# top.net
KiCad netlist of a schematic drawn in EAGLE
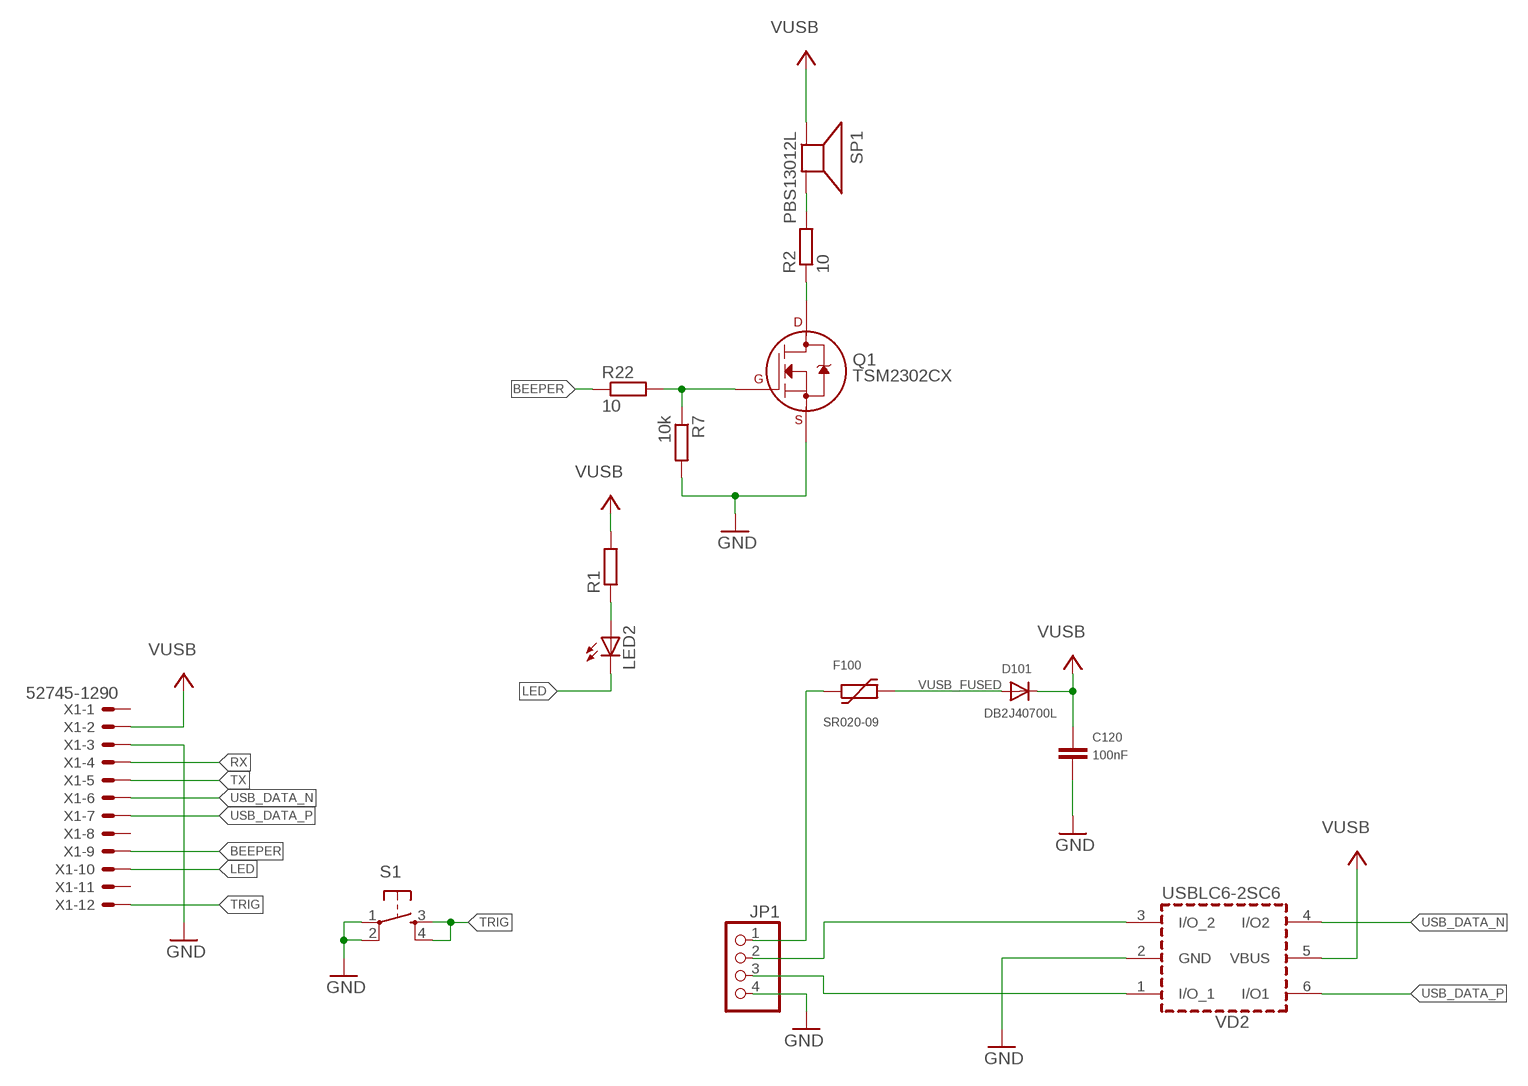
[diagram p0: schematic, sheet 1]

(export (version "E")
  (design (tool "Eeschema 10.0.6"))
  (components
    (comp (ref "C120")
      (value "100nF")
      (footprint "eagle-import:C0603K")
      (libsource (lib "eagle-import") (part "C-EUC0603K"))
    )
    (comp (ref "D101")
      (value "DB2J40700L")
      (footprint "eagle-import:SOD-323F")
      (libsource (lib "eagle-import") (part "DIODESOD-323F"))
    )
    (comp (ref "F100")
      (value "SR020-09")
      (footprint "eagle-import:PTC0805")
      (libsource (lib "eagle-import") (part "FUSE_PTC-0805"))
    )
    (comp (ref "JP1")
      (value "PINHD-1X4")
      (footprint "eagle-import:1X04")
      (libsource (lib "eagle-import") (part "PINHD-1X4"))
    )
    (comp (ref "LED2")
      (value "LEDCHIP-LED0805")
      (footprint "eagle-import:CHIP-LED0805")
      (libsource (lib "eagle-import") (part "LEDCHIP-LED0805"))
    )
    (comp (ref "Q1")
      (value "TSM2302CX")
      (footprint "eagle-import:SOT-23")
      (libsource (lib "eagle-import") (part "2N700_SOT232A"))
    )
    (comp (ref "R1")
      (value "R-EU_R0603")
      (footprint "eagle-import:R0603")
      (libsource (lib "eagle-import") (part "R-EU_R0603"))
    )
    (comp (ref "R2")
      (value "10")
      (footprint "eagle-import:R0603")
      (libsource (lib "eagle-import") (part "R-EU_R0603"))
    )
    (comp (ref "R7")
      (value "10k")
      (footprint "eagle-import:R0603")
      (libsource (lib "eagle-import") (part "R-EU_R0603"))
    )
    (comp (ref "R22")
      (value "10")
      (footprint "eagle-import:R0603")
      (libsource (lib "eagle-import") (part "R-EU_R0603"))
    )
    (comp (ref "S1")
      (value "TAC_SWITCHSMD")
      (footprint "eagle-import:TACTILE_SWITCH_SMD")
      (libsource (lib "eagle-import") (part "TAC_SWITCHSMD"))
    )
    (comp (ref "SP1")
      (value "PBS13012L")
      (footprint "eagle-import:AL60P")
      (libsource (lib "eagle-import") (part "SPEAKER/AL60P"))
    )
    (comp (ref "VD2")
      (value "USBLC6-2SC6")
      (footprint "eagle-import:SOT-23-6L")
      (libsource (lib "eagle-import") (part "USBLC6-2SC6"))
    )
    (comp (ref "X1")
      (value "52745-1290")
      (footprint "eagle-import:52745-1290")
      (libsource (lib "eagle-import") (part "52745-1290"))
    )
  )
  (nets
    (net (code "1") (name "/VUSB_FUSED") (class "Default")
      (node (ref "D101") (pin "A") (pinfunction "A_A") (pintype "passive"))
      (node (ref "F100") (pin "2") (pinfunction "2_2") (pintype "passive"))
    )
    (net (code "2") (name "BEEPER") (class "Default")
      (node (ref "R22") (pin "1") (pinfunction "1_1") (pintype "passive"))
      (node (ref "X1") (pin "9") (pinfunction "S_9") (pintype "passive"))
    )
    (net (code "3") (name "GND") (class "Default")
      (node (ref "C120") (pin "2") (pinfunction "2_2") (pintype "passive"))
      (node (ref "JP1") (pin "4") (pinfunction "4_4") (pintype "passive"))
      (node (ref "Q1") (pin "2") (pinfunction "S_2") (pintype "bidirectional"))
      (node (ref "R7") (pin "2") (pinfunction "2_2") (pintype "passive"))
      (node (ref "S1") (pin "1") (pinfunction "1_1") (pintype "passive"))
      (node (ref "S1") (pin "2") (pinfunction "2_2") (pintype "passive"))
      (node (ref "VD2") (pin "2") (pinfunction "GND_2") (pintype "bidirectional"))
      (node (ref "X1") (pin "3") (pinfunction "S_3") (pintype "passive"))
    )
    (net (code "4") (name "LED") (class "Default")
      (node (ref "LED2") (pin "C") (pinfunction "C_C") (pintype "passive"))
      (node (ref "X1") (pin "10") (pinfunction "S_10") (pintype "passive"))
    )
    (net (code "5") (name "Net-(F100-Pad1)") (class "Default")
      (node (ref "F100") (pin "1") (pinfunction "1_1") (pintype "passive"))
      (node (ref "JP1") (pin "1") (pinfunction "1_1") (pintype "passive"))
    )
    (net (code "6") (name "Net-(LED2-PadA)") (class "Default")
      (node (ref "LED2") (pin "A") (pinfunction "A_A") (pintype "passive"))
      (node (ref "R1") (pin "1") (pinfunction "1_1") (pintype "passive"))
    )
    (net (code "7") (name "Net-(Q1-D)") (class "Default")
      (node (ref "Q1") (pin "3") (pinfunction "D_3") (pintype "bidirectional"))
      (node (ref "R2") (pin "1") (pinfunction "1_1") (pintype "passive"))
    )
    (net (code "8") (name "Net-(Q1-G)") (class "Default")
      (node (ref "Q1") (pin "1") (pinfunction "G_1") (pintype "tri_state"))
      (node (ref "R22") (pin "2") (pinfunction "2_2") (pintype "passive"))
      (node (ref "R7") (pin "1") (pinfunction "1_1") (pintype "passive"))
    )
    (net (code "9") (name "Net-(SP1--)") (class "Default")
      (node (ref "R2") (pin "2") (pinfunction "2_2") (pintype "passive"))
      (node (ref "SP1") (pin "2") (pinfunction "-_2") (pintype "passive"))
    )
    (net (code "10") (name "Net-(VD2-I{slash}O_1)") (class "Default")
      (node (ref "JP1") (pin "3") (pinfunction "3_3") (pintype "passive"))
      (node (ref "VD2") (pin "1") (pinfunction "I/O_1_1") (pintype "bidirectional"))
    )
    (net (code "11") (name "Net-(VD2-I{slash}O_2)") (class "Default")
      (node (ref "JP1") (pin "2") (pinfunction "2_2") (pintype "passive"))
      (node (ref "VD2") (pin "3") (pinfunction "I/O_2_3") (pintype "bidirectional"))
    )
    (net (code "12") (name "RX") (class "Default")
      (node (ref "X1") (pin "4") (pinfunction "S_4") (pintype "passive"))
    )
    (net (code "13") (name "TRIG") (class "Default")
      (node (ref "S1") (pin "3") (pinfunction "3_3") (pintype "passive"))
      (node (ref "S1") (pin "4") (pinfunction "4_4") (pintype "passive"))
      (node (ref "X1") (pin "12") (pinfunction "S_12") (pintype "passive"))
    )
    (net (code "14") (name "TX") (class "Default")
      (node (ref "X1") (pin "5") (pinfunction "S_5") (pintype "passive"))
    )
    (net (code "15") (name "USB_DATA_N") (class "Default")
      (node (ref "VD2") (pin "4") (pinfunction "I/O2_4") (pintype "bidirectional"))
      (node (ref "X1") (pin "6") (pinfunction "S_6") (pintype "passive"))
    )
    (net (code "16") (name "USB_DATA_P") (class "Default")
      (node (ref "VD2") (pin "6") (pinfunction "I/O1_6") (pintype "bidirectional"))
      (node (ref "X1") (pin "7") (pinfunction "S_7") (pintype "passive"))
    )
    (net (code "17") (name "VUSB") (class "Default")
      (node (ref "C120") (pin "1") (pinfunction "1_1") (pintype "passive"))
      (node (ref "D101") (pin "C") (pinfunction "C_C") (pintype "passive"))
      (node (ref "R1") (pin "2") (pinfunction "2_2") (pintype "passive"))
      (node (ref "SP1") (pin "1") (pinfunction "+_1") (pintype "passive"))
      (node (ref "VD2") (pin "5") (pinfunction "VBUS_5") (pintype "bidirectional"))
      (node (ref "X1") (pin "2") (pinfunction "S_2") (pintype "passive"))
    )
    (net (code "18") (name "unconnected-(X1A-S-Pad1)") (class "Default")
      (node (ref "X1") (pin "1") (pinfunction "S_1") (pintype "passive"))
    )
    (net (code "19") (name "unconnected-(X1C-S-Pad11)") (class "Default")
      (node (ref "X1") (pin "11") (pinfunction "S_11") (pintype "passive"))
    )
    (net (code "20") (name "unconnected-(X1K-S-Pad8)") (class "Default")
      (node (ref "X1") (pin "8") (pinfunction "S_8") (pintype "passive"))
    )
  )
)
